# top.net
KiCad netlist of a schematic drawn in Altium Designer
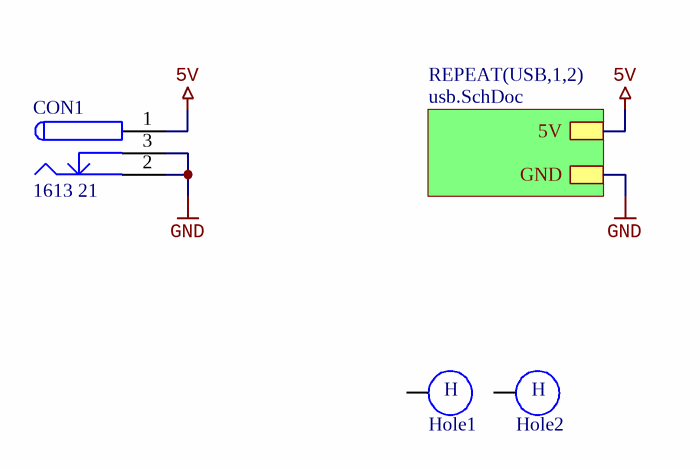
[diagram p0: top.SchDoc]

(export (version "E")
  (design (tool "Eeschema 10.0.6"))
  (components
    (comp (ref "CON1")
      (value "1613 21")
      (footprint "JACK-2.5")
      (description "Low Voltage Power Supply Connector")
      (libsource (lib "connectors") (part "JACK-2.5"))
    )
    (comp (ref "Hole1") (value "Hole") (footprint "HOLE-6/3.2") (libsource (lib "misc") (part "HOLE_")))
    (comp (ref "Hole2") (value "Hole") (footprint "HOLE-6/3.2") (libsource (lib "misc") (part "HOLE_")))
  )
  (nets
    (net (code "1") (name "5V") (class "Default")
      (node (ref "CON1") (pin "1") (pinfunction "1_1") (pintype "power_in"))
    )
    (net (code "2") (name "GND") (class "Default")
      (node (ref "CON1") (pin "2") (pinfunction "2_2") (pintype "power_in"))
      (node (ref "CON1") (pin "3") (pinfunction "3_3") (pintype "passive"))
    )
    (net (code "3") (name "unconnected-(Hole1-Pad1)") (class "Default")
      (node (ref "Hole1") (pin "1") (pinfunction "1_1") (pintype "passive"))
    )
    (net (code "4") (name "unconnected-(Hole2-Pad1)") (class "Default")
      (node (ref "Hole2") (pin "1") (pinfunction "1_1") (pintype "passive"))
    )
  )
)
